# mSD-Shield_v12.net
KiCad netlist of a schematic drawn in EAGLE
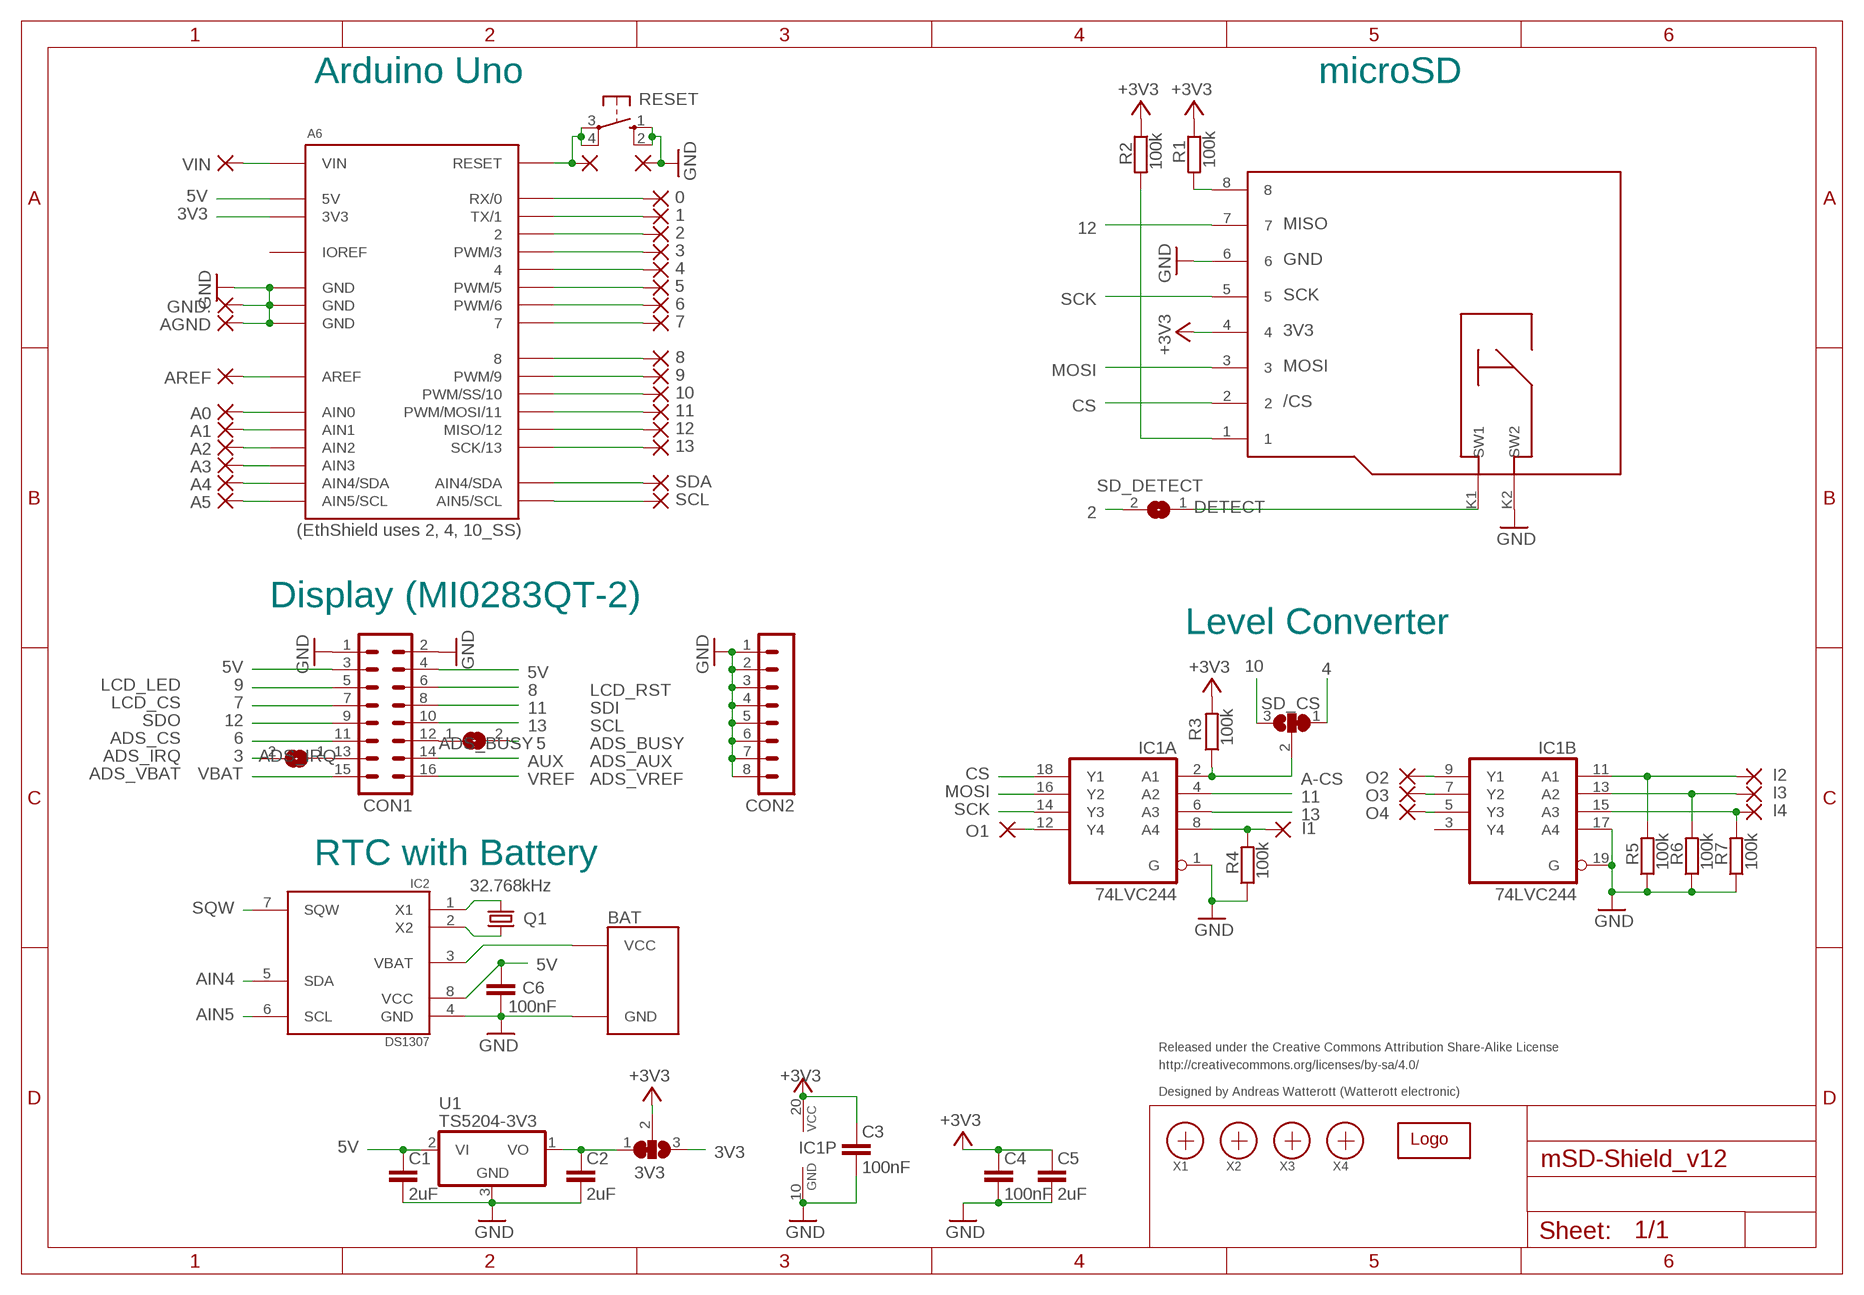
[diagram p0: schematic, sheet 1]

(export (version "E")
  (design (tool "Eeschema 10.0.6"))
  (components
    (comp (ref "0")
      (value "1,6/0,8")
      (footprint "eagle-import:1,6_0,8")
      (libsource (lib "eagle-import") (part "1,6/0,8"))
    )
    (comp (ref "1")
      (value "1,6/0,8")
      (footprint "eagle-import:1,6_0,8")
      (libsource (lib "eagle-import") (part "1,6/0,8"))
    )
    (comp (ref "2")
      (value "1,6/0,8")
      (footprint "eagle-import:1,6_0,8")
      (libsource (lib "eagle-import") (part "1,6/0,8"))
    )
    (comp (ref "3")
      (value "1,6/0,8")
      (footprint "eagle-import:1,6_0,8")
      (libsource (lib "eagle-import") (part "1,6/0,8"))
    )
    (comp (ref "3V3")
      (value "SJ2W")
      (footprint "eagle-import:SJ_2")
      (libsource (lib "eagle-import") (part "SJ2W"))
    )
    (comp (ref "4")
      (value "1,6/0,8")
      (footprint "eagle-import:1,6_0,8")
      (libsource (lib "eagle-import") (part "1,6/0,8"))
    )
    (comp (ref "5")
      (value "1,6/0,8")
      (footprint "eagle-import:1,6_0,8")
      (libsource (lib "eagle-import") (part "1,6/0,8"))
    )
    (comp (ref "6")
      (value "1,6/0,8")
      (footprint "eagle-import:1,6_0,8")
      (libsource (lib "eagle-import") (part "1,6/0,8"))
    )
    (comp (ref "7")
      (value "1,6/0,8")
      (footprint "eagle-import:1,6_0,8")
      (libsource (lib "eagle-import") (part "1,6/0,8"))
    )
    (comp (ref "8")
      (value "1,6/0,8")
      (footprint "eagle-import:1,6_0,8")
      (libsource (lib "eagle-import") (part "1,6/0,8"))
    )
    (comp (ref "9")
      (value "1,6/0,8")
      (footprint "eagle-import:1,6_0,8")
      (libsource (lib "eagle-import") (part "1,6/0,8"))
    )
    (comp (ref "10")
      (value "1,6/0,8")
      (footprint "eagle-import:1,6_0,8")
      (libsource (lib "eagle-import") (part "1,6/0,8"))
    )
    (comp (ref "11")
      (value "1,6/0,8")
      (footprint "eagle-import:1,6_0,8")
      (libsource (lib "eagle-import") (part "1,6/0,8"))
    )
    (comp (ref "12")
      (value "1,6/0,8")
      (footprint "eagle-import:1,6_0,8")
      (libsource (lib "eagle-import") (part "1,6/0,8"))
    )
    (comp (ref "13")
      (value "1,6/0,8")
      (footprint "eagle-import:1,6_0,8")
      (libsource (lib "eagle-import") (part "1,6/0,8"))
    )
    (comp (ref "A0")
      (value "1,6/0,8")
      (footprint "eagle-import:1,6_0,8")
      (libsource (lib "eagle-import") (part "1,6/0,8"))
    )
    (comp (ref "A1")
      (value "1,6/0,8")
      (footprint "eagle-import:1,6_0,8")
      (libsource (lib "eagle-import") (part "1,6/0,8"))
    )
    (comp (ref "A2")
      (value "1,6/0,8")
      (footprint "eagle-import:1,6_0,8")
      (libsource (lib "eagle-import") (part "1,6/0,8"))
    )
    (comp (ref "A3")
      (value "1,6/0,8")
      (footprint "eagle-import:1,6_0,8")
      (libsource (lib "eagle-import") (part "1,6/0,8"))
    )
    (comp (ref "A4")
      (value "1,6/0,8")
      (footprint "eagle-import:1,6_0,8")
      (libsource (lib "eagle-import") (part "1,6/0,8"))
    )
    (comp (ref "A5")
      (value "1,6/0,8")
      (footprint "eagle-import:1,6_0,8")
      (libsource (lib "eagle-import") (part "1,6/0,8"))
    )
    (comp (ref "A6")
      (value "UNO2")
      (footprint "eagle-import:UNO2")
      (libsource (lib "eagle-import") (part "UNO2"))
    )
    (comp (ref "ADS_BUSY")
      (value "SJ")
      (footprint "eagle-import:SJ")
      (libsource (lib "eagle-import") (part "SJ"))
    )
    (comp (ref "ADS_IRQ")
      (value "SJ")
      (footprint "eagle-import:SJ")
      (libsource (lib "eagle-import") (part "SJ"))
    )
    (comp (ref "AGND")
      (value "1,6/0,8")
      (footprint "eagle-import:1,6_0,8")
      (libsource (lib "eagle-import") (part "1,6/0,8"))
    )
    (comp (ref "AREF")
      (value "1,6/0,8")
      (footprint "eagle-import:1,6_0,8")
      (libsource (lib "eagle-import") (part "1,6/0,8"))
    )
    (comp (ref "BAT")
      (value "4UC-05581")
      (footprint "eagle-import:4UC-05581")
      (libsource (lib "eagle-import") (part "4UC-05581"))
    )
    (comp (ref "C1")
      (value "2uF")
      (footprint "eagle-import:C0805")
      (libsource (lib "eagle-import") (part "C-EUC0805"))
    )
    (comp (ref "C2")
      (value "2uF")
      (footprint "eagle-import:C0805")
      (libsource (lib "eagle-import") (part "C-EUC0805"))
    )
    (comp (ref "C3")
      (value "100nF")
      (footprint "eagle-import:C0603")
      (libsource (lib "eagle-import") (part "C-EUC0603"))
    )
    (comp (ref "C4")
      (value "100nF")
      (footprint "eagle-import:C0603")
      (libsource (lib "eagle-import") (part "C-EUC0603"))
    )
    (comp (ref "C5")
      (value "2uF")
      (footprint "eagle-import:C0603")
      (libsource (lib "eagle-import") (part "C-EUC0603"))
    )
    (comp (ref "C6")
      (value "100nF")
      (footprint "eagle-import:C0603")
      (libsource (lib "eagle-import") (part "C-EUC0603"))
    )
    (comp (ref "CON1")
      (value "MA08-2")
      (footprint "eagle-import:MA08-2")
      (libsource (lib "eagle-import") (part "MA08-2"))
    )
    (comp (ref "CON2")
      (value "MA08-1")
      (footprint "eagle-import:MA08-1")
      (libsource (lib "eagle-import") (part "MA08-1"))
    )
    (comp (ref "GND")
      (value "SMD2")
      (footprint "eagle-import:SMD1,27-2,54")
      (libsource (lib "eagle-import") (part "SMD2"))
    )
    (comp (ref "GND.")
      (value "1,6/0,8")
      (footprint "eagle-import:1,6_0,8")
      (libsource (lib "eagle-import") (part "1,6/0,8"))
    )
    (comp (ref "I1")
      (value "SMD2")
      (footprint "eagle-import:SMD1,27-2,54")
      (libsource (lib "eagle-import") (part "SMD2"))
    )
    (comp (ref "I2")
      (value "SMD2")
      (footprint "eagle-import:SMD1,27-2,54")
      (libsource (lib "eagle-import") (part "SMD2"))
    )
    (comp (ref "I3")
      (value "SMD2")
      (footprint "eagle-import:SMD1,27-2,54")
      (libsource (lib "eagle-import") (part "SMD2"))
    )
    (comp (ref "I4")
      (value "SMD2")
      (footprint "eagle-import:SMD1,27-2,54")
      (libsource (lib "eagle-import") (part "SMD2"))
    )
    (comp (ref "IC1")
      (value "74LVC244")
      (footprint "eagle-import:SO20W")
      (libsource (lib "eagle-import") (part "74244DWHC"))
    )
    (comp (ref "IC2")
      (value "DS1307")
      (footprint "eagle-import:SO8")
      (libsource (lib "eagle-import") (part "DS1307"))
    )
    (comp (ref "O1")
      (value "SMD2")
      (footprint "eagle-import:SMD1,27-2,54")
      (libsource (lib "eagle-import") (part "SMD2"))
    )
    (comp (ref "O2")
      (value "SMD2")
      (footprint "eagle-import:SMD1,27-2,54")
      (libsource (lib "eagle-import") (part "SMD2"))
    )
    (comp (ref "O3")
      (value "SMD2")
      (footprint "eagle-import:SMD1,27-2,54")
      (libsource (lib "eagle-import") (part "SMD2"))
    )
    (comp (ref "O4")
      (value "SMD2")
      (footprint "eagle-import:SMD1,27-2,54")
      (libsource (lib "eagle-import") (part "SMD2"))
    )
    (comp (ref "Q1")
      (value "32.768kHz")
      (footprint "eagle-import:TC26V")
      (libsource (lib "eagle-import") (part "CRYSTALTC26V"))
    )
    (comp (ref "R1")
      (value "100k")
      (footprint "eagle-import:R0603")
      (libsource (lib "eagle-import") (part "R-EU_R0603"))
    )
    (comp (ref "R2")
      (value "100k")
      (footprint "eagle-import:R0603")
      (libsource (lib "eagle-import") (part "R-EU_R0603"))
    )
    (comp (ref "R3")
      (value "100k")
      (footprint "eagle-import:R0603")
      (libsource (lib "eagle-import") (part "R-EU_R0603"))
    )
    (comp (ref "R4")
      (value "100k")
      (footprint "eagle-import:R0603")
      (libsource (lib "eagle-import") (part "R-EU_R0603"))
    )
    (comp (ref "R5")
      (value "100k")
      (footprint "eagle-import:R0603")
      (libsource (lib "eagle-import") (part "R-EU_R0603"))
    )
    (comp (ref "R6")
      (value "100k")
      (footprint "eagle-import:R0603")
      (libsource (lib "eagle-import") (part "R-EU_R0603"))
    )
    (comp (ref "R7")
      (value "100k")
      (footprint "eagle-import:R0603")
      (libsource (lib "eagle-import") (part "R-EU_R0603"))
    )
    (comp (ref "RESET")
      (value "10-XX")
      (footprint "eagle-import:B3F-10XX")
      (fields (field (name "MPN") "B3F-1000"))
      (libsource (lib "eagle-import") (part "10-XX"))
    )
    (comp (ref "RST")
      (value "SMD2")
      (footprint "eagle-import:SMD1,27-2,54")
      (libsource (lib "eagle-import") (part "SMD2"))
    )
    (comp (ref "SCL")
      (value "1,6/0,8")
      (footprint "eagle-import:1,6_0,8")
      (libsource (lib "eagle-import") (part "1,6/0,8"))
    )
    (comp (ref "SDA")
      (value "1,6/0,8")
      (footprint "eagle-import:1,6_0,8")
      (libsource (lib "eagle-import") (part "1,6/0,8"))
    )
    (comp (ref "SD_CS")
      (value "SJ2W")
      (footprint "eagle-import:SJ_2")
      (libsource (lib "eagle-import") (part "SJ2W"))
    )
    (comp (ref "SD_DETECT")
      (value "SJ")
      (footprint "eagle-import:SJ")
      (libsource (lib "eagle-import") (part "SJ"))
    )
    (comp (ref "U$1")
      (value "WE-LOGO")
      (footprint "eagle-import:WE-LOGO")
      (libsource (lib "eagle-import") (part "WE-LOGO"))
    )
    (comp (ref "U1")
      (value "TS5204-3V3")
      (footprint "eagle-import:SOT23")
      (libsource (lib "eagle-import") (part "TS5204"))
    )
    (comp (ref "VIN")
      (value "1,6/0,8")
      (footprint "eagle-import:1,6_0,8")
      (libsource (lib "eagle-import") (part "1,6/0,8"))
    )
    (comp (ref "X1")
      (value "PASSER")
      (footprint "eagle-import:PASSER")
      (libsource (lib "eagle-import") (part "PASSER"))
    )
    (comp (ref "X2")
      (value "PASSER")
      (footprint "eagle-import:PASSER")
      (libsource (lib "eagle-import") (part "PASSER"))
    )
    (comp (ref "X3")
      (value "PASSER")
      (footprint "eagle-import:PASSER")
      (libsource (lib "eagle-import") (part "PASSER"))
    )
    (comp (ref "X4")
      (value "PASSER")
      (footprint "eagle-import:PASSER")
      (libsource (lib "eagle-import") (part "PASSER"))
    )
    (comp (ref "X5")
      (value "MICRO-SD")
      (footprint "eagle-import:MICRO-SD")
      (libsource (lib "eagle-import") (part "MICRO-SD"))
    )
  )
  (nets
    (net (code "1") (name "+3V3") (class "Default")
      (node (ref "3V3") (pin "2") (pinfunction "2_2") (pintype "passive"))
      (node (ref "C3") (pin "1") (pinfunction "1_1") (pintype "passive"))
      (node (ref "C4") (pin "1") (pinfunction "1_1") (pintype "passive"))
      (node (ref "C5") (pin "1") (pinfunction "1_1") (pintype "passive"))
      (node (ref "IC1") (pin "20") (pinfunction "VCC_20") (pintype "power_in"))
      (node (ref "R1") (pin "1") (pinfunction "1_1") (pintype "passive"))
      (node (ref "R2") (pin "1") (pinfunction "1_1") (pintype "passive"))
      (node (ref "R3") (pin "2") (pinfunction "2_2") (pintype "passive"))
      (node (ref "X5") (pin "4") (pinfunction "4_4") (pintype "bidirectional"))
    )
    (net (code "2") (name "/2") (class "Default")
      (node (ref "2") (pin "1") (pinfunction "P_1") (pintype "passive"))
      (node (ref "A6") (pin "2") (pinfunction "2_2") (pintype "bidirectional"))
      (node (ref "SD_DETECT") (pin "2") (pinfunction "2_2") (pintype "passive"))
    )
    (net (code "3") (name "/3") (class "Default")
      (node (ref "3") (pin "1") (pinfunction "P_1") (pintype "passive"))
      (node (ref "A6") (pin "3") (pinfunction "PWM/3_3") (pintype "bidirectional"))
      (node (ref "ADS_IRQ") (pin "2") (pinfunction "2_2") (pintype "passive"))
    )
    (net (code "4") (name "/3V3") (class "Default")
      (node (ref "3V3") (pin "3") (pinfunction "3_3") (pintype "passive"))
      (node (ref "A6") (pin "3V3") (pinfunction "3V3_3V3") (pintype "power_in"))
    )
    (net (code "5") (name "/4") (class "Default")
      (node (ref "4") (pin "1") (pinfunction "P_1") (pintype "passive"))
      (node (ref "A6") (pin "4") (pinfunction "4_4") (pintype "bidirectional"))
      (node (ref "SD_CS") (pin "1") (pinfunction "1_1") (pintype "passive"))
    )
    (net (code "6") (name "/5") (class "Default")
      (node (ref "5") (pin "1") (pinfunction "P_1") (pintype "passive"))
      (node (ref "A6") (pin "5") (pinfunction "PWM/5_5") (pintype "bidirectional"))
      (node (ref "ADS_BUSY") (pin "2") (pinfunction "2_2") (pintype "passive"))
    )
    (net (code "7") (name "/5V") (class "Default")
      (node (ref "A6") (pin "5V") (pinfunction "5V_5V") (pintype "power_in"))
      (node (ref "C1") (pin "1") (pinfunction "1_1") (pintype "passive"))
      (node (ref "C6") (pin "2") (pinfunction "2_2") (pintype "passive"))
      (node (ref "CON1") (pin "3") (pinfunction "3_3") (pintype "passive"))
      (node (ref "CON1") (pin "4") (pinfunction "4_4") (pintype "passive"))
      (node (ref "IC2") (pin "8") (pinfunction "VCC_8") (pintype "power_in"))
      (node (ref "U1") (pin "2") (pinfunction "VI_2") (pintype "input"))
    )
    (net (code "8") (name "/6") (class "Default")
      (node (ref "6") (pin "1") (pinfunction "P_1") (pintype "passive"))
      (node (ref "A6") (pin "6") (pinfunction "PWM/6_6") (pintype "bidirectional"))
      (node (ref "CON1") (pin "11") (pinfunction "11_11") (pintype "passive"))
    )
    (net (code "9") (name "/7") (class "Default")
      (node (ref "7") (pin "1") (pinfunction "P_1") (pintype "passive"))
      (node (ref "A6") (pin "7") (pinfunction "7_7") (pintype "bidirectional"))
      (node (ref "CON1") (pin "7") (pinfunction "7_7") (pintype "passive"))
    )
    (net (code "10") (name "/8") (class "Default")
      (node (ref "8") (pin "1") (pinfunction "P_1") (pintype "passive"))
      (node (ref "A6") (pin "8") (pinfunction "8_8") (pintype "bidirectional"))
      (node (ref "CON1") (pin "6") (pinfunction "6_6") (pintype "passive"))
    )
    (net (code "11") (name "/9") (class "Default")
      (node (ref "9") (pin "1") (pinfunction "P_1") (pintype "passive"))
      (node (ref "A6") (pin "9") (pinfunction "PWM/9_9") (pintype "bidirectional"))
      (node (ref "CON1") (pin "5") (pinfunction "5_5") (pintype "passive"))
    )
    (net (code "12") (name "/10") (class "Default")
      (node (ref "10") (pin "1") (pinfunction "P_1") (pintype "passive"))
      (node (ref "A6") (pin "10") (pinfunction "PWM/SS/10_10") (pintype "bidirectional"))
      (node (ref "SD_CS") (pin "3") (pinfunction "3_3") (pintype "passive"))
    )
    (net (code "13") (name "/11") (class "Default")
      (node (ref "11") (pin "1") (pinfunction "P_1") (pintype "passive"))
      (node (ref "A6") (pin "11") (pinfunction "PWM/MOSI/11_11") (pintype "bidirectional"))
      (node (ref "CON1") (pin "8") (pinfunction "8_8") (pintype "passive"))
      (node (ref "IC1") (pin "4") (pinfunction "A2_4") (pintype "input"))
    )
    (net (code "14") (name "/12") (class "Default")
      (node (ref "12") (pin "1") (pinfunction "P_1") (pintype "passive"))
      (node (ref "A6") (pin "12") (pinfunction "MISO/12_12") (pintype "bidirectional"))
      (node (ref "CON1") (pin "9") (pinfunction "9_9") (pintype "passive"))
      (node (ref "X5") (pin "7") (pinfunction "7_7") (pintype "bidirectional"))
    )
    (net (code "15") (name "/13") (class "Default")
      (node (ref "13") (pin "1") (pinfunction "P_1") (pintype "passive"))
      (node (ref "A6") (pin "13") (pinfunction "SCK/13_13") (pintype "bidirectional"))
      (node (ref "CON1") (pin "10") (pinfunction "10_10") (pintype "passive"))
      (node (ref "IC1") (pin "6") (pinfunction "A3_6") (pintype "input"))
    )
    (net (code "16") (name "/A-CS") (class "Default")
      (node (ref "IC1") (pin "2") (pinfunction "A1_2") (pintype "input"))
      (node (ref "R3") (pin "1") (pinfunction "1_1") (pintype "passive"))
      (node (ref "SD_CS") (pin "2") (pinfunction "2_2") (pintype "passive"))
    )
    (net (code "17") (name "/AIN4") (class "Default")
      (node (ref "A4") (pin "1") (pinfunction "P_1") (pintype "passive"))
      (node (ref "A6") (pin "AIN4") (pinfunction "AIN4/SDA_AIN4") (pintype "bidirectional"))
      (node (ref "IC2") (pin "5") (pinfunction "SDA_5") (pintype "bidirectional"))
    )
    (net (code "18") (name "/AIN5") (class "Default")
      (node (ref "A5") (pin "1") (pinfunction "P_1") (pintype "passive"))
      (node (ref "A6") (pin "AIN5") (pinfunction "AIN5/SCL_AIN5") (pintype "bidirectional"))
      (node (ref "IC2") (pin "6") (pinfunction "SCL_6") (pintype "bidirectional"))
    )
    (net (code "19") (name "/AUX") (class "Default")
      (node (ref "CON1") (pin "14") (pinfunction "14_14") (pintype "passive"))
    )
    (net (code "20") (name "/CS") (class "Default")
      (node (ref "IC1") (pin "18") (pinfunction "Y1_18") (pintype "tri_state"))
      (node (ref "X5") (pin "2") (pinfunction "2_2") (pintype "bidirectional"))
    )
    (net (code "21") (name "/DETECT") (class "Default")
      (node (ref "SD_DETECT") (pin "1") (pinfunction "1_1") (pintype "passive"))
      (node (ref "X5") (pin "K1") (pinfunction "SW1_K1") (pintype "bidirectional"))
    )
    (net (code "22") (name "/IOREF") (class "Default")
      (node (ref "A6") (pin "IOREF") (pinfunction "IOREF_IOREF") (pintype "power_in"))
    )
    (net (code "23") (name "/MOSI") (class "Default")
      (node (ref "IC1") (pin "16") (pinfunction "Y2_16") (pintype "tri_state"))
      (node (ref "X5") (pin "3") (pinfunction "3_3") (pintype "bidirectional"))
    )
    (net (code "24") (name "/SCK") (class "Default")
      (node (ref "IC1") (pin "14") (pinfunction "Y3_14") (pintype "tri_state"))
      (node (ref "X5") (pin "5") (pinfunction "5_5") (pintype "bidirectional"))
    )
    (net (code "25") (name "/SQW") (class "Default")
      (node (ref "IC2") (pin "7") (pinfunction "SQW_7") (pintype "bidirectional"))
    )
    (net (code "26") (name "/VBAT") (class "Default")
      (node (ref "CON1") (pin "15") (pinfunction "15_15") (pintype "passive"))
    )
    (net (code "27") (name "/VREF") (class "Default")
      (node (ref "CON1") (pin "16") (pinfunction "16_16") (pintype "passive"))
    )
    (net (code "28") (name "GND") (class "Default")
      (node (ref "A6") (pin "GND@1") (pinfunction "GND_GND@1") (pintype "power_in"))
      (node (ref "A6") (pin "GND@2") (pinfunction "GND_GND@2") (pintype "power_in"))
      (node (ref "A6") (pin "GND@3") (pinfunction "GND_GND@3") (pintype "power_in"))
      (node (ref "AGND") (pin "1") (pinfunction "P_1") (pintype "passive"))
      (node (ref "BAT") (pin "GND") (pinfunction "GND_GND") (pintype "power_in"))
      (node (ref "C1") (pin "2") (pinfunction "2_2") (pintype "passive"))
      (node (ref "C2") (pin "2") (pinfunction "2_2") (pintype "passive"))
      (node (ref "C3") (pin "2") (pinfunction "2_2") (pintype "passive"))
      (node (ref "C4") (pin "2") (pinfunction "2_2") (pintype "passive"))
      (node (ref "C5") (pin "2") (pinfunction "2_2") (pintype "passive"))
      (node (ref "C6") (pin "1") (pinfunction "1_1") (pintype "passive"))
      (node (ref "CON1") (pin "1") (pinfunction "1_1") (pintype "passive"))
      (node (ref "CON1") (pin "2") (pinfunction "2_2") (pintype "passive"))
      (node (ref "CON2") (pin "1") (pinfunction "1_1") (pintype "passive"))
      (node (ref "CON2") (pin "2") (pinfunction "2_2") (pintype "passive"))
      (node (ref "CON2") (pin "3") (pinfunction "3_3") (pintype "passive"))
      (node (ref "CON2") (pin "4") (pinfunction "4_4") (pintype "passive"))
      (node (ref "CON2") (pin "5") (pinfunction "5_5") (pintype "passive"))
      (node (ref "CON2") (pin "6") (pinfunction "6_6") (pintype "passive"))
      (node (ref "CON2") (pin "7") (pinfunction "7_7") (pintype "passive"))
      (node (ref "CON2") (pin "8") (pinfunction "8_8") (pintype "passive"))
      (node (ref "GND") (pin "1") (pinfunction "P_1") (pintype "passive"))
      (node (ref "GND.") (pin "1") (pinfunction "P_1") (pintype "passive"))
      (node (ref "IC1") (pin "1") (pinfunction "G_1") (pintype "input"))
      (node (ref "IC1") (pin "10") (pinfunction "GND_10") (pintype "power_in"))
      (node (ref "IC1") (pin "17") (pinfunction "A4_17") (pintype "input"))
      (node (ref "IC1") (pin "19") (pinfunction "G_19") (pintype "input"))
      (node (ref "IC2") (pin "4") (pinfunction "GND_4") (pintype "power_in"))
      (node (ref "R4") (pin "1") (pinfunction "1_1") (pintype "passive"))
      (node (ref "R5") (pin "1") (pinfunction "1_1") (pintype "passive"))
      (node (ref "R6") (pin "1") (pinfunction "1_1") (pintype "passive"))
      (node (ref "R7") (pin "1") (pinfunction "1_1") (pintype "passive"))
      (node (ref "RESET") (pin "1") (pinfunction "S_1") (pintype "passive"))
      (node (ref "RESET") (pin "2") (pinfunction "S1_2") (pintype "passive"))
      (node (ref "U1") (pin "3") (pinfunction "GND_3") (pintype "passive"))
      (node (ref "X5") (pin "6") (pinfunction "6_6") (pintype "bidirectional"))
      (node (ref "X5") (pin "K2") (pinfunction "SW2_K2") (pintype "bidirectional"))
    )
    (net (code "29") (name "Net-(0-P)") (class "Default")
      (node (ref "0") (pin "1") (pinfunction "P_1") (pintype "passive"))
      (node (ref "A6") (pin "0") (pinfunction "RX/0_0") (pintype "bidirectional"))
    )
    (net (code "30") (name "Net-(1-P)") (class "Default")
      (node (ref "1") (pin "1") (pinfunction "P_1") (pintype "passive"))
      (node (ref "A6") (pin "1") (pinfunction "TX/1_1") (pintype "bidirectional"))
    )
    (net (code "31") (name "Net-(A0-P)") (class "Default")
      (node (ref "A0") (pin "1") (pinfunction "P_1") (pintype "passive"))
      (node (ref "A6") (pin "AIN0") (pinfunction "AIN0_AIN0") (pintype "bidirectional"))
    )
    (net (code "32") (name "Net-(A1-P)") (class "Default")
      (node (ref "A1") (pin "1") (pinfunction "P_1") (pintype "passive"))
      (node (ref "A6") (pin "AIN1") (pinfunction "AIN1_AIN1") (pintype "bidirectional"))
    )
    (net (code "33") (name "Net-(A2-P)") (class "Default")
      (node (ref "A2") (pin "1") (pinfunction "P_1") (pintype "passive"))
      (node (ref "A6") (pin "AIN2") (pinfunction "AIN2_AIN2") (pintype "bidirectional"))
    )
    (net (code "34") (name "Net-(A3-P)") (class "Default")
      (node (ref "A3") (pin "1") (pinfunction "P_1") (pintype "passive"))
      (node (ref "A6") (pin "AIN3") (pinfunction "AIN3_AIN3") (pintype "bidirectional"))
    )
    (net (code "35") (name "Net-(A6-RESET)") (class "Default")
      (node (ref "A6") (pin "RST") (pinfunction "RESET_RST") (pintype "bidirectional"))
      (node (ref "RESET") (pin "3") (pinfunction "P_3") (pintype "passive"))
      (node (ref "RESET") (pin "4") (pinfunction "P1_4") (pintype "passive"))
      (node (ref "RST") (pin "1") (pinfunction "P_1") (pintype "passive"))
    )
    (net (code "36") (name "Net-(ADS_BUSY-Pad1)") (class "Default")
      (node (ref "ADS_BUSY") (pin "1") (pinfunction "1_1") (pintype "passive"))
      (node (ref "CON1") (pin "12") (pinfunction "12_12") (pintype "passive"))
    )
    (net (code "37") (name "Net-(ADS_IRQ-Pad1)") (class "Default")
      (node (ref "ADS_IRQ") (pin "1") (pinfunction "1_1") (pintype "passive"))
      (node (ref "CON1") (pin "13") (pinfunction "13_13") (pintype "passive"))
    )
    (net (code "38") (name "Net-(AREF-P)") (class "Default")
      (node (ref "A6") (pin "AREF") (pinfunction "AREF_AREF") (pintype "power_in"))
      (node (ref "AREF") (pin "1") (pinfunction "P_1") (pintype "passive"))
    )
    (net (code "39") (name "Net-(I1-P)") (class "Default")
      (node (ref "I1") (pin "1") (pinfunction "P_1") (pintype "passive"))
      (node (ref "IC1") (pin "8") (pinfunction "A4_8") (pintype "input"))
      (node (ref "R4") (pin "2") (pinfunction "2_2") (pintype "passive"))
    )
    (net (code "40") (name "Net-(I2-P)") (class "Default")
      (node (ref "I2") (pin "1") (pinfunction "P_1") (pintype "passive"))
      (node (ref "IC1") (pin "11") (pinfunction "A1_11") (pintype "input"))
      (node (ref "R5") (pin "2") (pinfunction "2_2") (pintype "passive"))
    )
    (net (code "41") (name "Net-(I3-P)") (class "Default")
      (node (ref "I3") (pin "1") (pinfunction "P_1") (pintype "passive"))
      (node (ref "IC1") (pin "13") (pinfunction "A2_13") (pintype "input"))
      (node (ref "R6") (pin "2") (pinfunction "2_2") (pintype "passive"))
    )
    (net (code "42") (name "Net-(I4-P)") (class "Default")
      (node (ref "I4") (pin "1") (pinfunction "P_1") (pintype "passive"))
      (node (ref "IC1") (pin "15") (pinfunction "A3_15") (pintype "input"))
      (node (ref "R7") (pin "2") (pinfunction "2_2") (pintype "passive"))
    )
    (net (code "43") (name "Net-(IC1A-Y4)") (class "Default")
      (node (ref "IC1") (pin "12") (pinfunction "Y4_12") (pintype "tri_state"))
      (node (ref "O1") (pin "1") (pinfunction "P_1") (pintype "passive"))
    )
    (net (code "44") (name "Net-(IC1B-Y1)") (class "Default")
      (node (ref "IC1") (pin "9") (pinfunction "Y1_9") (pintype "tri_state"))
      (node (ref "O2") (pin "1") (pinfunction "P_1") (pintype "passive"))
    )
    (net (code "45") (name "Net-(IC1B-Y2)") (class "Default")
      (node (ref "IC1") (pin "7") (pinfunction "Y2_7") (pintype "tri_state"))
      (node (ref "O3") (pin "1") (pinfunction "P_1") (pintype "passive"))
    )
    (net (code "46") (name "Net-(IC1B-Y3)") (class "Default")
      (node (ref "IC1") (pin "5") (pinfunction "Y3_5") (pintype "tri_state"))
      (node (ref "O4") (pin "1") (pinfunction "P_1") (pintype "passive"))
    )
    (net (code "47") (name "Net-(IC2-VBAT)") (class "Default")
      (node (ref "BAT") (pin "VCC") (pinfunction "VCC_VCC") (pintype "power_in"))
      (node (ref "IC2") (pin "3") (pinfunction "VBAT_3") (pintype "power_in"))
    )
    (net (code "48") (name "Net-(IC2-X1)") (class "Default")
      (node (ref "IC2") (pin "1") (pinfunction "X1_1") (pintype "bidirectional"))
      (node (ref "Q1") (pin "2") (pinfunction "2_2") (pintype "passive"))
    )
    (net (code "49") (name "Net-(IC2-X2)") (class "Default")
      (node (ref "IC2") (pin "2") (pinfunction "X2_2") (pintype "bidirectional"))
      (node (ref "Q1") (pin "1") (pinfunction "1_1") (pintype "passive"))
    )
    (net (code "50") (name "Net-(R1-Pad2)") (class "Default")
      (node (ref "R1") (pin "2") (pinfunction "2_2") (pintype "passive"))
      (node (ref "X5") (pin "8") (pinfunction "8_8") (pintype "bidirectional"))
    )
    (net (code "51") (name "Net-(R2-Pad2)") (class "Default")
      (node (ref "R2") (pin "2") (pinfunction "2_2") (pintype "passive"))
      (node (ref "X5") (pin "1") (pinfunction "1_1") (pintype "bidirectional"))
    )
    (net (code "52") (name "Net-(SCL-P)") (class "Default")
      (node (ref "A6") (pin "SCL") (pinfunction "AIN5/SCL_SCL") (pintype "bidirectional"))
      (node (ref "SCL") (pin "1") (pinfunction "P_1") (pintype "passive"))
    )
    (net (code "53") (name "Net-(SDA-P)") (class "Default")
      (node (ref "A6") (pin "SDA") (pinfunction "AIN4/SDA_SDA") (pintype "bidirectional"))
      (node (ref "SDA") (pin "1") (pinfunction "P_1") (pintype "passive"))
    )
    (net (code "54") (name "Net-(U1-VO)") (class "Default")
      (node (ref "3V3") (pin "1") (pinfunction "1_1") (pintype "passive"))
      (node (ref "C2") (pin "1") (pinfunction "1_1") (pintype "passive"))
      (node (ref "U1") (pin "1") (pinfunction "VO_1") (pintype "passive"))
    )
    (net (code "55") (name "Net-(VIN-P)") (class "Default")
      (node (ref "A6") (pin "VIN") (pinfunction "VIN_VIN") (pintype "power_in"))
      (node (ref "VIN") (pin "1") (pinfunction "P_1") (pintype "passive"))
    )
    (net (code "56") (name "unconnected-(IC1B-Y4-Pad3)") (class "Default")
      (node (ref "IC1") (pin "3") (pinfunction "Y4_3") (pintype "tri_state"))
    )
  )
)
